# pi2pci.net
KiCad netlist of a schematic drawn in Altium Designer
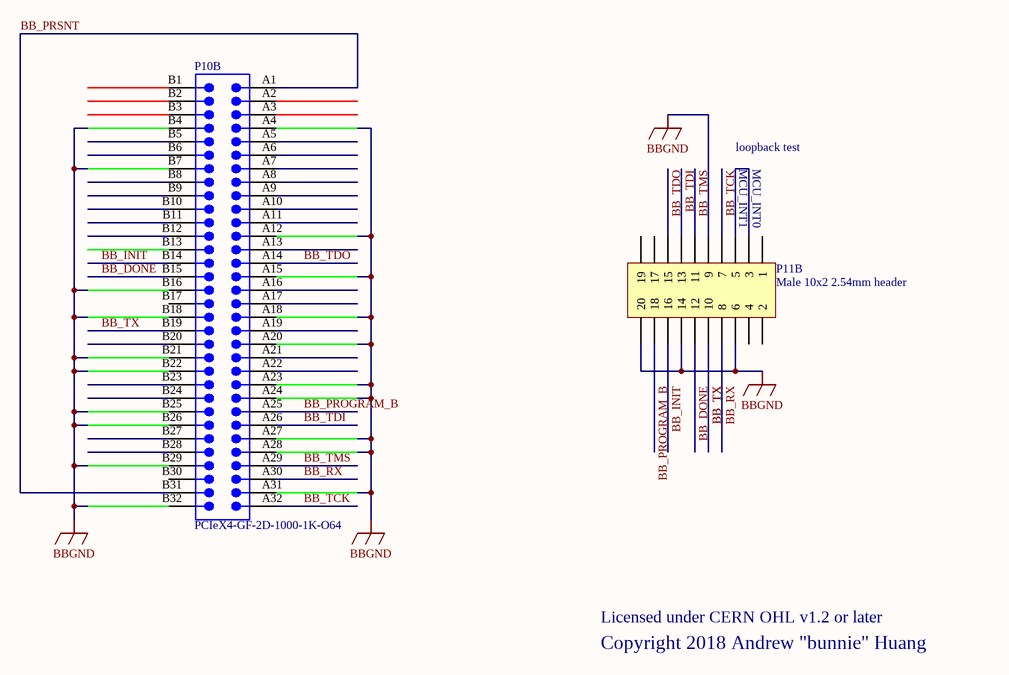
[diagram p0: pi2pci.SchDoc]

(export (version "E")
  (design (tool "Eeschema 10.0.6"))
  (components
    (comp (ref "P10B")
      (value "PCIeX4-GF-2D-1000-1K-O64")
      (footprint "PCIeX4-GF-2D-1000-1K-O64")
      (description "Golden finger, PCIeX4, Dual, Opposite, Pitch 1mm, 64-Position")
      (fields (field (name "PUBLISHER") "Altium"))
      (libsource (lib "altium-import") (part "root_3_CMP-0001-00031-1_"))
    )
    (comp (ref "P11B")
      (value "Male 10x2 2.54mm header")
      (footprint "HDR2X10")
      (description "Header, 10-Pin, Dual row")
      (fields (field (name "MPN") "CP25412-020-G116-A") (field (name "PUBLISHER") "Altium Limited"))
      (libsource (lib "Miscellaneous Connectors") (part "Header 10X2"))
    )
  )
  (nets
    (net (code "1") (name "/BB_DONE") (class "Default")
      (node (ref "P10B") (pin "B15") (pinfunction "B15_B15") (pintype "passive"))
      (node (ref "P11B") (pin "12") (pinfunction "12_12") (pintype "passive"))
    )
    (net (code "2") (name "/BB_INIT") (class "Default")
      (node (ref "P10B") (pin "B14") (pinfunction "B14_B14") (pintype "passive"))
      (node (ref "P11B") (pin "16") (pinfunction "16_16") (pintype "passive"))
    )
    (net (code "3") (name "/BB_PROGRAM_B") (class "Default")
      (node (ref "P10B") (pin "A25") (pinfunction "A25_A25") (pintype "passive"))
      (node (ref "P11B") (pin "18") (pinfunction "18_18") (pintype "passive"))
    )
    (net (code "4") (name "/BB_PRSNT") (class "Default")
      (node (ref "P10B") (pin "A1") (pinfunction "A1_A1") (pintype "passive"))
      (node (ref "P10B") (pin "B31") (pinfunction "B31_B31") (pintype "passive"))
    )
    (net (code "5") (name "/BB_RX") (class "Default")
      (node (ref "P10B") (pin "A30") (pinfunction "A30_A30") (pintype "passive"))
      (node (ref "P11B") (pin "8") (pinfunction "8_8") (pintype "passive"))
    )
    (net (code "6") (name "/BB_TCK") (class "Default")
      (node (ref "P10B") (pin "A32") (pinfunction "A32_A32") (pintype "passive"))
      (node (ref "P11B") (pin "7") (pinfunction "7_7") (pintype "passive"))
    )
    (net (code "7") (name "/BB_TDI") (class "Default")
      (node (ref "P10B") (pin "A26") (pinfunction "A26_A26") (pintype "passive"))
      (node (ref "P11B") (pin "13") (pinfunction "13_13") (pintype "passive"))
    )
    (net (code "8") (name "/BB_TDO") (class "Default")
      (node (ref "P10B") (pin "A14") (pinfunction "A14_A14") (pintype "passive"))
      (node (ref "P11B") (pin "15") (pinfunction "15_15") (pintype "passive"))
    )
    (net (code "9") (name "/BB_TMS") (class "Default")
      (node (ref "P10B") (pin "A29") (pinfunction "A29_A29") (pintype "passive"))
      (node (ref "P11B") (pin "11") (pinfunction "11_11") (pintype "passive"))
    )
    (net (code "10") (name "/BB_TX") (class "Default")
      (node (ref "P10B") (pin "B19") (pinfunction "B19_B19") (pintype "passive"))
      (node (ref "P11B") (pin "10") (pinfunction "10_10") (pintype "passive"))
    )
    (net (code "11") (name "BBGND") (class "Default")
      (node (ref "P10B") (pin "A12") (pinfunction "A12_A12") (pintype "passive"))
      (node (ref "P10B") (pin "A15") (pinfunction "A15_A15") (pintype "passive"))
      (node (ref "P10B") (pin "A18") (pinfunction "A18_A18") (pintype "passive"))
      (node (ref "P10B") (pin "A20") (pinfunction "A20_A20") (pintype "passive"))
      (node (ref "P10B") (pin "A23") (pinfunction "A23_A23") (pintype "passive"))
      (node (ref "P10B") (pin "A24") (pinfunction "A24_A24") (pintype "passive"))
      (node (ref "P10B") (pin "A27") (pinfunction "A27_A27") (pintype "passive"))
      (node (ref "P10B") (pin "A28") (pinfunction "A28_A28") (pintype "passive"))
      (node (ref "P10B") (pin "A31") (pinfunction "A31_A31") (pintype "passive"))
      (node (ref "P10B") (pin "A4") (pinfunction "A4_A4") (pintype "passive"))
      (node (ref "P10B") (pin "B16") (pinfunction "B16_B16") (pintype "passive"))
      (node (ref "P10B") (pin "B18") (pinfunction "B18_B18") (pintype "passive"))
      (node (ref "P10B") (pin "B21") (pinfunction "B21_B21") (pintype "passive"))
      (node (ref "P10B") (pin "B22") (pinfunction "B22_B22") (pintype "passive"))
      (node (ref "P10B") (pin "B25") (pinfunction "B25_B25") (pintype "passive"))
      (node (ref "P10B") (pin "B26") (pinfunction "B26_B26") (pintype "passive"))
      (node (ref "P10B") (pin "B29") (pinfunction "B29_B29") (pintype "passive"))
      (node (ref "P10B") (pin "B32") (pinfunction "B32_B32") (pintype "passive"))
      (node (ref "P10B") (pin "B4") (pinfunction "B4_B4") (pintype "passive"))
      (node (ref "P10B") (pin "B7") (pinfunction "B7_B7") (pintype "passive"))
      (node (ref "P11B") (pin "14") (pinfunction "14_14") (pintype "passive"))
      (node (ref "P11B") (pin "20") (pinfunction "20_20") (pintype "passive"))
      (node (ref "P11B") (pin "6") (pinfunction "6_6") (pintype "passive"))
      (node (ref "P11B") (pin "9") (pinfunction "9_9") (pintype "passive"))
    )
    (net (code "12") (name "Net-(P11B-Pad3)") (class "Default")
      (node (ref "P11B") (pin "3") (pinfunction "3_3") (pintype "passive"))
      (node (ref "P11B") (pin "5") (pinfunction "5_5") (pintype "passive"))
    )
    (net (code "13") (name "unconnected-(P10B-PadA2)") (class "Default")
      (node (ref "P10B") (pin "A2") (pinfunction "A2_A2") (pintype "passive"))
    )
    (net (code "14") (name "unconnected-(P10B-PadA3)") (class "Default")
      (node (ref "P10B") (pin "A3") (pinfunction "A3_A3") (pintype "passive"))
    )
    (net (code "15") (name "unconnected-(P10B-PadA5)") (class "Default")
      (node (ref "P10B") (pin "A5") (pinfunction "A5_A5") (pintype "passive"))
    )
    (net (code "16") (name "unconnected-(P10B-PadA6)") (class "Default")
      (node (ref "P10B") (pin "A6") (pinfunction "A6_A6") (pintype "passive"))
    )
    (net (code "17") (name "unconnected-(P10B-PadA7)") (class "Default")
      (node (ref "P10B") (pin "A7") (pinfunction "A7_A7") (pintype "passive"))
    )
    (net (code "18") (name "unconnected-(P10B-PadA8)") (class "Default")
      (node (ref "P10B") (pin "A8") (pinfunction "A8_A8") (pintype "passive"))
    )
    (net (code "19") (name "unconnected-(P10B-PadA9)") (class "Default")
      (node (ref "P10B") (pin "A9") (pinfunction "A9_A9") (pintype "passive"))
    )
    (net (code "20") (name "unconnected-(P10B-PadA10)") (class "Default")
      (node (ref "P10B") (pin "A10") (pinfunction "A10_A10") (pintype "passive"))
    )
    (net (code "21") (name "unconnected-(P10B-PadA11)") (class "Default")
      (node (ref "P10B") (pin "A11") (pinfunction "A11_A11") (pintype "passive"))
    )
    (net (code "22") (name "unconnected-(P10B-PadA13)") (class "Default")
      (node (ref "P10B") (pin "A13") (pinfunction "A13_A13") (pintype "passive"))
    )
    (net (code "23") (name "unconnected-(P10B-PadA16)") (class "Default")
      (node (ref "P10B") (pin "A16") (pinfunction "A16_A16") (pintype "passive"))
    )
    (net (code "24") (name "unconnected-(P10B-PadA17)") (class "Default")
      (node (ref "P10B") (pin "A17") (pinfunction "A17_A17") (pintype "passive"))
    )
    (net (code "25") (name "unconnected-(P10B-PadA19)") (class "Default")
      (node (ref "P10B") (pin "A19") (pinfunction "A19_A19") (pintype "passive"))
    )
    (net (code "26") (name "unconnected-(P10B-PadA21)") (class "Default")
      (node (ref "P10B") (pin "A21") (pinfunction "A21_A21") (pintype "passive"))
    )
    (net (code "27") (name "unconnected-(P10B-PadA22)") (class "Default")
      (node (ref "P10B") (pin "A22") (pinfunction "A22_A22") (pintype "passive"))
    )
    (net (code "28") (name "unconnected-(P10B-PadB1)") (class "Default")
      (node (ref "P10B") (pin "B1") (pinfunction "B1_B1") (pintype "passive"))
    )
    (net (code "29") (name "unconnected-(P10B-PadB2)") (class "Default")
      (node (ref "P10B") (pin "B2") (pinfunction "B2_B2") (pintype "passive"))
    )
    (net (code "30") (name "unconnected-(P10B-PadB3)") (class "Default")
      (node (ref "P10B") (pin "B3") (pinfunction "B3_B3") (pintype "passive"))
    )
    (net (code "31") (name "unconnected-(P10B-PadB5)") (class "Default")
      (node (ref "P10B") (pin "B5") (pinfunction "B5_B5") (pintype "passive"))
    )
    (net (code "32") (name "unconnected-(P10B-PadB6)") (class "Default")
      (node (ref "P10B") (pin "B6") (pinfunction "B6_B6") (pintype "passive"))
    )
    (net (code "33") (name "unconnected-(P10B-PadB8)") (class "Default")
      (node (ref "P10B") (pin "B8") (pinfunction "B8_B8") (pintype "passive"))
    )
    (net (code "34") (name "unconnected-(P10B-PadB9)") (class "Default")
      (node (ref "P10B") (pin "B9") (pinfunction "B9_B9") (pintype "passive"))
    )
    (net (code "35") (name "unconnected-(P10B-PadB10)") (class "Default")
      (node (ref "P10B") (pin "B10") (pinfunction "B10_B10") (pintype "passive"))
    )
    (net (code "36") (name "unconnected-(P10B-PadB11)") (class "Default")
      (node (ref "P10B") (pin "B11") (pinfunction "B11_B11") (pintype "passive"))
    )
    (net (code "37") (name "unconnected-(P10B-PadB12)") (class "Default")
      (node (ref "P10B") (pin "B12") (pinfunction "B12_B12") (pintype "passive"))
    )
    (net (code "38") (name "unconnected-(P10B-PadB13)") (class "Default")
      (node (ref "P10B") (pin "B13") (pinfunction "B13_B13") (pintype "passive"))
    )
    (net (code "39") (name "unconnected-(P10B-PadB17)") (class "Default")
      (node (ref "P10B") (pin "B17") (pinfunction "B17_B17") (pintype "passive"))
    )
    (net (code "40") (name "unconnected-(P10B-PadB20)") (class "Default")
      (node (ref "P10B") (pin "B20") (pinfunction "B20_B20") (pintype "passive"))
    )
    (net (code "41") (name "unconnected-(P10B-PadB23)") (class "Default")
      (node (ref "P10B") (pin "B23") (pinfunction "B23_B23") (pintype "passive"))
    )
    (net (code "42") (name "unconnected-(P10B-PadB24)") (class "Default")
      (node (ref "P10B") (pin "B24") (pinfunction "B24_B24") (pintype "passive"))
    )
    (net (code "43") (name "unconnected-(P10B-PadB27)") (class "Default")
      (node (ref "P10B") (pin "B27") (pinfunction "B27_B27") (pintype "passive"))
    )
    (net (code "44") (name "unconnected-(P10B-PadB28)") (class "Default")
      (node (ref "P10B") (pin "B28") (pinfunction "B28_B28") (pintype "passive"))
    )
    (net (code "45") (name "unconnected-(P10B-PadB30)") (class "Default")
      (node (ref "P10B") (pin "B30") (pinfunction "B30_B30") (pintype "passive"))
    )
    (net (code "46") (name "unconnected-(P11B-Pad1)") (class "Default")
      (node (ref "P11B") (pin "1") (pinfunction "1_1") (pintype "passive"))
    )
    (net (code "47") (name "unconnected-(P11B-Pad2)") (class "Default")
      (node (ref "P11B") (pin "2") (pinfunction "2_2") (pintype "passive"))
    )
    (net (code "48") (name "unconnected-(P11B-Pad4)") (class "Default")
      (node (ref "P11B") (pin "4") (pinfunction "4_4") (pintype "passive"))
    )
    (net (code "49") (name "unconnected-(P11B-Pad17)") (class "Default")
      (node (ref "P11B") (pin "17") (pinfunction "17_17") (pintype "passive"))
    )
    (net (code "50") (name "unconnected-(P11B-Pad19)") (class "Default")
      (node (ref "P11B") (pin "19") (pinfunction "19_19") (pintype "passive"))
    )
  )
)
